# toy.net
KiCad netlist of a schematic drawn in EAGLE
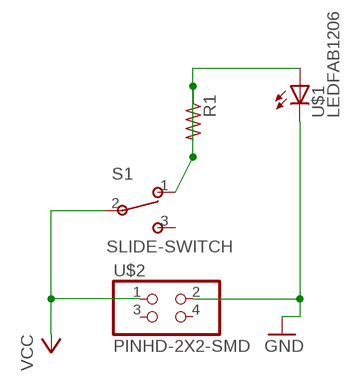
[diagram p0: schematic, sheet 1]

(export (version "E")
  (design (tool "Eeschema 10.0.6"))
  (components
    (comp (ref "R1")
      (value "RES-US1206FAB")
      (footprint "eagle-import:R1206FAB")
      (libsource (lib "eagle-import") (part "RES-US1206FAB"))
    )
    (comp (ref "S1")
      (value "SLIDE-SWITCH")
      (footprint "eagle-import:AYZ0102AGRLC")
      (libsource (lib "eagle-import") (part "SLIDE-SWITCH"))
    )
    (comp (ref "U$1")
      (value "LEDFAB1206")
      (footprint "eagle-import:LED1206FAB")
      (libsource (lib "eagle-import") (part "LEDFAB1206"))
    )
    (comp (ref "U$2")
      (value "PINHD-2X2-SMD")
      (footprint "eagle-import:2X02SMD")
      (libsource (lib "eagle-import") (part "PINHD-2X2-SMD"))
    )
  )
  (nets
    (net (code "1") (name "GND") (class "Default")
      (node (ref "U$1") (pin "2") (pinfunction "C_2") (pintype "passive"))
      (node (ref "U$2") (pin "2") (pinfunction "2_2") (pintype "passive"))
    )
    (net (code "2") (name "Net-(U$1-A)") (class "Default")
      (node (ref "R1") (pin "1") (pinfunction "1_1") (pintype "passive"))
      (node (ref "R1") (pin "2") (pinfunction "2_2") (pintype "passive"))
      (node (ref "S1") (pin "1") (pinfunction "1_1") (pintype "bidirectional"))
      (node (ref "U$1") (pin "1") (pinfunction "A_1") (pintype "passive"))
    )
    (net (code "3") (name "VCC") (class "Default")
      (node (ref "S1") (pin "2") (pinfunction "2_2") (pintype "bidirectional"))
      (node (ref "U$2") (pin "1") (pinfunction "1_1") (pintype "passive"))
    )
    (net (code "4") (name "unconnected-(S1-Pad3)") (class "Default")
      (node (ref "S1") (pin "3") (pinfunction "3_3") (pintype "bidirectional"))
    )
    (net (code "5") (name "unconnected-(U$2-Pad3)") (class "Default")
      (node (ref "U$2") (pin "3") (pinfunction "3_3") (pintype "passive"))
    )
    (net (code "6") (name "unconnected-(U$2-Pad4)") (class "Default")
      (node (ref "U$2") (pin "4") (pinfunction "4_4") (pintype "passive"))
    )
  )
)
